# dual_sensor_module.net
KiCad netlist of a schematic drawn in EAGLE
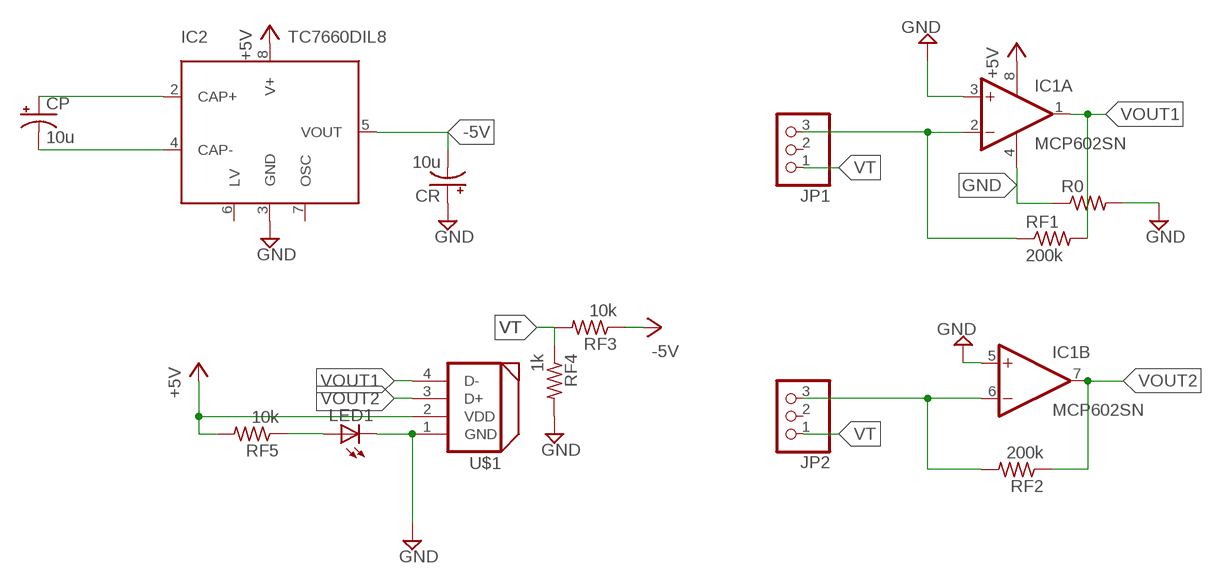
[diagram p0: schematic, sheet 1]

(export (version "E")
  (design (tool "Eeschema 10.0.6"))
  (components
    (comp (ref "CP")
      (value "10u")
      (footprint "eagle-import:E2,5-5")
      (libsource (lib "eagle-import") (part "CPOL-USE2.5-5"))
    )
    (comp (ref "CR")
      (value "10u")
      (footprint "eagle-import:E2,5-5")
      (libsource (lib "eagle-import") (part "CPOL-USE2.5-5"))
    )
    (comp (ref "IC1")
      (value "MCP602SN")
      (footprint "eagle-import:SO08")
      (libsource (lib "eagle-import") (part "MCP602SN"))
    )
    (comp (ref "IC2")
      (value "TC7660DIL8")
      (footprint "eagle-import:DIL8")
      (libsource (lib "eagle-import") (part "TC7660DIL8"))
    )
    (comp (ref "JP1")
      (value "PINHD-1X3")
      (footprint "eagle-import:1X03")
      (libsource (lib "eagle-import") (part "PINHD-1X3"))
    )
    (comp (ref "JP2")
      (value "PINHD-1X3")
      (footprint "eagle-import:1X03")
      (libsource (lib "eagle-import") (part "PINHD-1X3"))
    )
    (comp (ref "LED1")
      (value "LEDCHIPLED_0805")
      (footprint "eagle-import:CHIPLED_0805")
      (libsource (lib "eagle-import") (part "LEDCHIPLED_0805"))
    )
    (comp (ref "R0")
      (value "R-US_R1206")
      (footprint "eagle-import:R1206")
      (libsource (lib "eagle-import") (part "R-US_R1206"))
    )
    (comp (ref "RF1")
      (value "200k")
      (footprint "eagle-import:R0805")
      (libsource (lib "eagle-import") (part "resistor_348_R-US_R0805"))
    )
    (comp (ref "RF2")
      (value "200k")
      (footprint "eagle-import:R0805")
      (libsource (lib "eagle-import") (part "resistor_348_R-US_R0805"))
    )
    (comp (ref "RF3")
      (value "10k")
      (footprint "eagle-import:R0805")
      (libsource (lib "eagle-import") (part "resistor_348_R-US_R0805"))
    )
    (comp (ref "RF4")
      (value "1k")
      (footprint "eagle-import:R0805")
      (libsource (lib "eagle-import") (part "resistor_348_R-US_R0805"))
    )
    (comp (ref "RF5")
      (value "10k")
      (footprint "eagle-import:R0805")
      (libsource (lib "eagle-import") (part "resistor_348_R-US_R0805"))
    )
    (comp (ref "U$1")
      (value "DYNAMIXEL_RS485")
      (footprint "eagle-import:DYNAMIXEL_SPOX_04")
      (libsource (lib "eagle-import") (part "DYNAMIXEL_RS485"))
    )
  )
  (nets
    (net (code "1") (name "+5V") (class "Default")
      (node (ref "IC1") (pin "8") (pinfunction "V+_8") (pintype "power_in"))
      (node (ref "IC2") (pin "8") (pinfunction "V+_8") (pintype "bidirectional"))
      (node (ref "RF5") (pin "2") (pinfunction "2_2") (pintype "passive"))
      (node (ref "U$1") (pin "2") (pinfunction "VDD_2") (pintype "power_in"))
    )
    (net (code "2") (name "-5V") (class "Default")
      (node (ref "CR") (pin "-") (pinfunction "-_-") (pintype "passive"))
      (node (ref "IC2") (pin "5") (pinfunction "VOUT_5") (pintype "bidirectional"))
      (node (ref "RF3") (pin "1") (pinfunction "1_1") (pintype "passive"))
    )
    (net (code "3") (name "GND") (class "Default")
      (node (ref "CR") (pin "+") (pinfunction "+_+") (pintype "passive"))
      (node (ref "IC1") (pin "3") (pinfunction "+IN_3") (pintype "input"))
      (node (ref "IC1") (pin "4") (pinfunction "V-_4") (pintype "power_in"))
      (node (ref "IC1") (pin "5") (pinfunction "+IN_5") (pintype "input"))
      (node (ref "IC2") (pin "3") (pinfunction "GND_3") (pintype "bidirectional"))
      (node (ref "LED1") (pin "C") (pinfunction "C_C") (pintype "passive"))
      (node (ref "R0") (pin "1") (pinfunction "1_1") (pintype "passive"))
      (node (ref "R0") (pin "2") (pinfunction "2_2") (pintype "passive"))
      (node (ref "RF4") (pin "2") (pinfunction "2_2") (pintype "passive"))
      (node (ref "U$1") (pin "1") (pinfunction "GND_1") (pintype "power_in"))
    )
    (net (code "4") (name "Net-(IC1A--IN)") (class "Default")
      (node (ref "IC1") (pin "2") (pinfunction "-IN_2") (pintype "input"))
      (node (ref "JP1") (pin "3") (pinfunction "3_3") (pintype "passive"))
      (node (ref "RF1") (pin "1") (pinfunction "1_1") (pintype "passive"))
    )
    (net (code "5") (name "Net-(IC1B--IN)") (class "Default")
      (node (ref "IC1") (pin "6") (pinfunction "-IN_6") (pintype "input"))
      (node (ref "JP2") (pin "3") (pinfunction "3_3") (pintype "passive"))
      (node (ref "RF2") (pin "2") (pinfunction "2_2") (pintype "passive"))
    )
    (net (code "6") (name "Net-(IC2-CAP+)") (class "Default")
      (node (ref "CP") (pin "+") (pinfunction "+_+") (pintype "passive"))
      (node (ref "IC2") (pin "2") (pinfunction "CAP+_2") (pintype "bidirectional"))
    )
    (net (code "7") (name "Net-(IC2-CAP-)") (class "Default")
      (node (ref "CP") (pin "-") (pinfunction "-_-") (pintype "passive"))
      (node (ref "IC2") (pin "4") (pinfunction "CAP-_4") (pintype "bidirectional"))
    )
    (net (code "8") (name "Net-(LED1-PadA)") (class "Default")
      (node (ref "LED1") (pin "A") (pinfunction "A_A") (pintype "passive"))
      (node (ref "RF5") (pin "1") (pinfunction "1_1") (pintype "passive"))
    )
    (net (code "9") (name "VOUT1") (class "Default")
      (node (ref "IC1") (pin "1") (pinfunction "OUT_1") (pintype "output"))
      (node (ref "RF1") (pin "2") (pinfunction "2_2") (pintype "passive"))
      (node (ref "U$1") (pin "4") (pinfunction "D-_4") (pintype "bidirectional"))
    )
    (net (code "10") (name "VOUT2") (class "Default")
      (node (ref "IC1") (pin "7") (pinfunction "OUT_7") (pintype "output"))
      (node (ref "RF2") (pin "1") (pinfunction "1_1") (pintype "passive"))
      (node (ref "U$1") (pin "3") (pinfunction "D+_3") (pintype "bidirectional"))
    )
    (net (code "11") (name "VT") (class "Default")
      (node (ref "JP1") (pin "1") (pinfunction "1_1") (pintype "passive"))
      (node (ref "JP2") (pin "1") (pinfunction "1_1") (pintype "passive"))
      (node (ref "RF3") (pin "2") (pinfunction "2_2") (pintype "passive"))
      (node (ref "RF4") (pin "1") (pinfunction "1_1") (pintype "passive"))
    )
    (net (code "12") (name "unconnected-(IC2-LV-Pad6)") (class "Default")
      (node (ref "IC2") (pin "6") (pinfunction "LV_6") (pintype "bidirectional"))
    )
    (net (code "13") (name "unconnected-(IC2-OSC-Pad7)") (class "Default")
      (node (ref "IC2") (pin "7") (pinfunction "OSC_7") (pintype "bidirectional"))
    )
    (net (code "14") (name "unconnected-(JP1-Pad2)") (class "Default")
      (node (ref "JP1") (pin "2") (pinfunction "2_2") (pintype "passive"))
    )
    (net (code "15") (name "unconnected-(JP2-Pad2)") (class "Default")
      (node (ref "JP2") (pin "2") (pinfunction "2_2") (pintype "passive"))
    )
  )
)
